# main.net
KiCad netlist of a schematic drawn in EAGLE
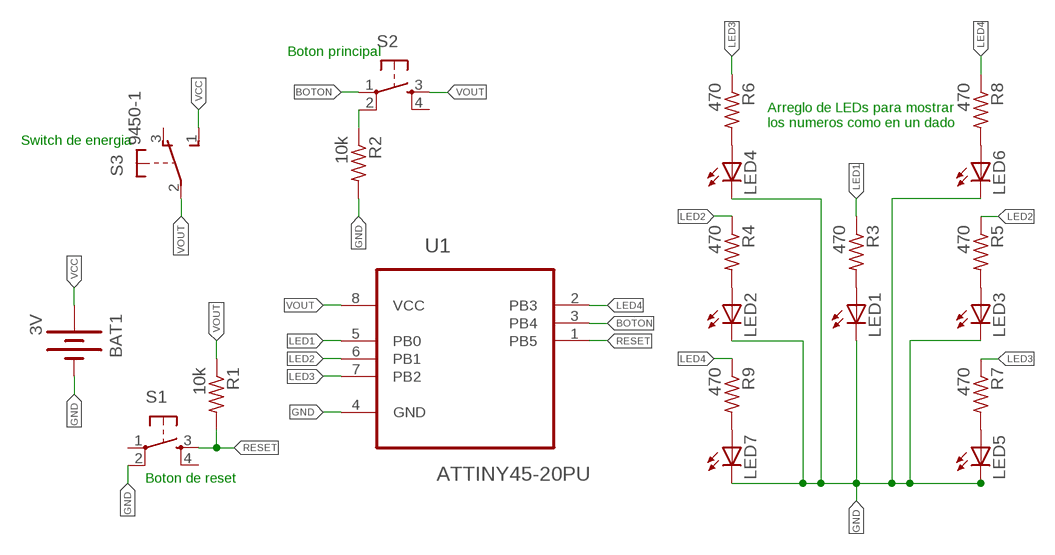
[diagram p0: schematic, sheet 1]

(export (version "E")
  (design (tool "Eeschema 10.0.6"))
  (components
    (comp (ref "BAT1")
      (value "3V")
      (footprint "eagle-import:BATTCOM_20MM_PTH")
      (libsource (lib "eagle-import") (part "BATTERY20PTH"))
    )
    (comp (ref "LED1")
      (value "LED5MM")
      (footprint "eagle-import:LED5MM")
      (libsource (lib "eagle-import") (part "LED5MM"))
    )
    (comp (ref "LED2")
      (value "LED5MM")
      (footprint "eagle-import:LED5MM")
      (libsource (lib "eagle-import") (part "LED5MM"))
    )
    (comp (ref "LED3")
      (value "LED5MM")
      (footprint "eagle-import:LED5MM")
      (libsource (lib "eagle-import") (part "LED5MM"))
    )
    (comp (ref "LED4")
      (value "LED5MM")
      (footprint "eagle-import:LED5MM")
      (libsource (lib "eagle-import") (part "LED5MM"))
    )
    (comp (ref "LED5")
      (value "LED5MM")
      (footprint "eagle-import:LED5MM")
      (libsource (lib "eagle-import") (part "LED5MM"))
    )
    (comp (ref "LED6")
      (value "LED5MM")
      (footprint "eagle-import:LED5MM")
      (libsource (lib "eagle-import") (part "LED5MM"))
    )
    (comp (ref "LED7")
      (value "LED5MM")
      (footprint "eagle-import:LED5MM")
      (libsource (lib "eagle-import") (part "LED5MM"))
    )
    (comp (ref "R1")
      (value "10k")
      (footprint "eagle-import:0204_5")
      (libsource (lib "eagle-import") (part "R-US_0204/5"))
    )
    (comp (ref "R2")
      (value "10k")
      (footprint "eagle-import:0204_5")
      (libsource (lib "eagle-import") (part "R-US_0204/5"))
    )
    (comp (ref "R3")
      (value "470")
      (footprint "eagle-import:0204_5")
      (libsource (lib "eagle-import") (part "R-US_0204/5"))
    )
    (comp (ref "R4")
      (value "470")
      (footprint "eagle-import:0204_5")
      (libsource (lib "eagle-import") (part "R-US_0204/5"))
    )
    (comp (ref "R5")
      (value "470")
      (footprint "eagle-import:0204_5")
      (libsource (lib "eagle-import") (part "R-US_0204/5"))
    )
    (comp (ref "R6")
      (value "470")
      (footprint "eagle-import:0204_5")
      (libsource (lib "eagle-import") (part "R-US_0204/5"))
    )
    (comp (ref "R7")
      (value "470")
      (footprint "eagle-import:0204_5")
      (libsource (lib "eagle-import") (part "R-US_0204/5"))
    )
    (comp (ref "R8")
      (value "470")
      (footprint "eagle-import:0204_5")
      (libsource (lib "eagle-import") (part "R-US_0204/5"))
    )
    (comp (ref "R9")
      (value "470")
      (footprint "eagle-import:0204_5")
      (libsource (lib "eagle-import") (part "R-US_0204/5"))
    )
    (comp (ref "S1")
      (value "TAC_SWITCHPTH")
      (footprint "eagle-import:TACTILE-PTH")
      (libsource (lib "eagle-import") (part "TAC_SWITCHPTH"))
    )
    (comp (ref "S2")
      (value "TAC_SWITCHPTH")
      (footprint "eagle-import:TACTILE-PTH")
      (libsource (lib "eagle-import") (part "TAC_SWITCHPTH"))
    )
    (comp (ref "S3")
      (value "9450-1")
      (footprint "eagle-import:9450-1")
      (libsource (lib "eagle-import") (part "9450-1"))
    )
    (comp (ref "U1")
      (value "ATTINY45-20PU")
      (footprint "eagle-import:DIP254P762X533-8")
      (libsource (lib "eagle-import") (part "ATTINY45-20PU"))
    )
  )
  (nets
    (net (code "1") (name "BOTON") (class "Default")
      (node (ref "S2") (pin "1") (pinfunction "1_1") (pintype "passive"))
      (node (ref "U1") (pin "3") (pinfunction "PB4_3") (pintype "bidirectional"))
    )
    (net (code "2") (name "GND") (class "Default")
      (node (ref "BAT1") (pin "2") (pinfunction "-_2") (pintype "power_in"))
      (node (ref "LED1") (pin "K") (pinfunction "C_K") (pintype "passive"))
      (node (ref "LED2") (pin "K") (pinfunction "C_K") (pintype "passive"))
      (node (ref "LED3") (pin "K") (pinfunction "C_K") (pintype "passive"))
      (node (ref "LED4") (pin "K") (pinfunction "C_K") (pintype "passive"))
      (node (ref "LED5") (pin "K") (pinfunction "C_K") (pintype "passive"))
      (node (ref "LED6") (pin "K") (pinfunction "C_K") (pintype "passive"))
      (node (ref "LED7") (pin "K") (pinfunction "C_K") (pintype "passive"))
      (node (ref "R2") (pin "2") (pinfunction "2_2") (pintype "passive"))
      (node (ref "S1") (pin "2") (pinfunction "2_2") (pintype "passive"))
      (node (ref "U1") (pin "4") (pinfunction "GND_4") (pintype "passive"))
    )
    (net (code "3") (name "LED1") (class "Default")
      (node (ref "R3") (pin "1") (pinfunction "1_1") (pintype "passive"))
      (node (ref "U1") (pin "5") (pinfunction "PB0_5") (pintype "bidirectional"))
    )
    (net (code "4") (name "LED2") (class "Default")
      (node (ref "R4") (pin "1") (pinfunction "1_1") (pintype "passive"))
      (node (ref "R5") (pin "1") (pinfunction "1_1") (pintype "passive"))
      (node (ref "U1") (pin "6") (pinfunction "PB1_6") (pintype "bidirectional"))
    )
    (net (code "5") (name "LED3") (class "Default")
      (node (ref "R6") (pin "1") (pinfunction "1_1") (pintype "passive"))
      (node (ref "R7") (pin "1") (pinfunction "1_1") (pintype "passive"))
      (node (ref "U1") (pin "7") (pinfunction "PB2_7") (pintype "bidirectional"))
    )
    (net (code "6") (name "LED4") (class "Default")
      (node (ref "R8") (pin "1") (pinfunction "1_1") (pintype "passive"))
      (node (ref "R9") (pin "1") (pinfunction "1_1") (pintype "passive"))
      (node (ref "U1") (pin "2") (pinfunction "PB3_2") (pintype "bidirectional"))
    )
    (net (code "7") (name "Net-(LED1-PadA)") (class "Default")
      (node (ref "LED1") (pin "A") (pinfunction "A_A") (pintype "passive"))
      (node (ref "R3") (pin "2") (pinfunction "2_2") (pintype "passive"))
    )
    (net (code "8") (name "Net-(LED2-PadA)") (class "Default")
      (node (ref "LED2") (pin "A") (pinfunction "A_A") (pintype "passive"))
      (node (ref "R4") (pin "2") (pinfunction "2_2") (pintype "passive"))
    )
    (net (code "9") (name "Net-(LED3-PadA)") (class "Default")
      (node (ref "LED3") (pin "A") (pinfunction "A_A") (pintype "passive"))
      (node (ref "R5") (pin "2") (pinfunction "2_2") (pintype "passive"))
    )
    (net (code "10") (name "Net-(LED4-PadA)") (class "Default")
      (node (ref "LED4") (pin "A") (pinfunction "A_A") (pintype "passive"))
      (node (ref "R6") (pin "2") (pinfunction "2_2") (pintype "passive"))
    )
    (net (code "11") (name "Net-(LED5-PadA)") (class "Default")
      (node (ref "LED5") (pin "A") (pinfunction "A_A") (pintype "passive"))
      (node (ref "R7") (pin "2") (pinfunction "2_2") (pintype "passive"))
    )
    (net (code "12") (name "Net-(LED6-PadA)") (class "Default")
      (node (ref "LED6") (pin "A") (pinfunction "A_A") (pintype "passive"))
      (node (ref "R8") (pin "2") (pinfunction "2_2") (pintype "passive"))
    )
    (net (code "13") (name "Net-(LED7-PadA)") (class "Default")
      (node (ref "LED7") (pin "A") (pinfunction "A_A") (pintype "passive"))
      (node (ref "R9") (pin "2") (pinfunction "2_2") (pintype "passive"))
    )
    (net (code "14") (name "Net-(R2-Pad1)") (class "Default")
      (node (ref "R2") (pin "1") (pinfunction "1_1") (pintype "passive"))
      (node (ref "S2") (pin "2") (pinfunction "2_2") (pintype "passive"))
    )
    (net (code "15") (name "RESET") (class "Default")
      (node (ref "R1") (pin "2") (pinfunction "2_2") (pintype "passive"))
      (node (ref "S1") (pin "3") (pinfunction "3_3") (pintype "passive"))
      (node (ref "U1") (pin "1") (pinfunction "PB5_1") (pintype "bidirectional"))
    )
    (net (code "16") (name "VCC") (class "Default")
      (node (ref "BAT1") (pin "1") (pinfunction "+_1") (pintype "power_in"))
      (node (ref "S3") (pin "1") (pinfunction "S_1") (pintype "passive"))
    )
    (net (code "17") (name "VOUT") (class "Default")
      (node (ref "R1") (pin "1") (pinfunction "1_1") (pintype "passive"))
      (node (ref "S2") (pin "3") (pinfunction "3_3") (pintype "passive"))
      (node (ref "S3") (pin "2") (pinfunction "P_2") (pintype "passive"))
      (node (ref "U1") (pin "8") (pinfunction "VCC_8") (pintype "power_in"))
    )
    (net (code "18") (name "unconnected-(S1-Pad1)") (class "Default")
      (node (ref "S1") (pin "1") (pinfunction "1_1") (pintype "passive"))
    )
    (net (code "19") (name "unconnected-(S1-Pad4)") (class "Default")
      (node (ref "S1") (pin "4") (pinfunction "4_4") (pintype "passive"))
    )
    (net (code "20") (name "unconnected-(S2-Pad4)") (class "Default")
      (node (ref "S2") (pin "4") (pinfunction "4_4") (pintype "passive"))
    )
    (net (code "21") (name "unconnected-(S3-O-Pad3)") (class "Default")
      (node (ref "S3") (pin "3") (pinfunction "O_3") (pintype "passive"))
    )
  )
)
